# 5V_BOOST.net
KiCad netlist of a schematic drawn in Altium Designer
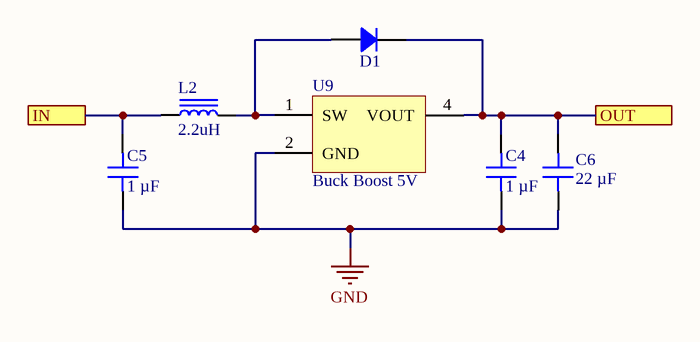
[diagram p0: 5V_BOOST.SchDoc]

(export (version "E")
  (design (tool "Eeschema 10.0.6"))
  (components
    (comp (ref "C4")
      (value "1 µF")
      (footprint "CAP 0402_1005")
      (description "CAP CER 0.1UF 16V X7R 0402")
      (fields (field (name "PART NUMBER") "C0402C104K4RACAUTO") (field (name "MANUFACTURER") "KEMET"))
      (libsource (lib "Celestial Altium Library - altium_library") (part "Capacitor"))
    )
    (comp (ref "C5")
      (value "1 µF")
      (footprint "CAP 0402_1005")
      (description "CAP CER 0.1UF 16V X7R 0402")
      (fields (field (name "PART NUMBER") "C0402C104K4RACAUTO") (field (name "MANUFACTURER") "KEMET"))
      (libsource (lib "Celestial Altium Library - altium_library") (part "Capacitor"))
    )
    (comp (ref "C6")
      (value "22 µF")
      (footprint "CAP 0805_2012")
      (description "CAP CER 22UF 10V X6S 0805")
      (fields
        (field (name "PART NUMBER") "GRM21BC81A226ME44L")
        (field (name "MANUFACTURER") "Murata Electronics")
      )
      (libsource (lib "Celestial Altium Library - altium_library") (part "Capacitor"))
    )
    (comp (ref "D1")
      (value "V1F6-M3/H")
      (footprint "SMF DO-219AB")
      (description "1A 60V SMF TRENCH SKY RECT")
      (fields (field (name "MANUFACTURER") "Vishay Semiconductor Diodes Division"))
      (libsource (lib "Celestial Altium Library - altium_library") (part "Diode"))
    )
    (comp (ref "L2")
      (value "2.2uH")
      (footprint "TAIYO YUDEN MAMK2520T1R0M")
      (description "FIXED IND 470NH 3.2A 46 MOHM SMD")
      (fields (field (name "PART NUMBER") "MAKK2520TR47M") (field (name "MANUFACTURER") "Taiyo Yuden"))
      (libsource (lib "Celestial Altium Library - altium_library") (part "Inductor"))
    )
    (comp (ref "U9")
      (value "Buck Boost 5V")
      (footprint "TI SOT-23-5 DBV")
      (description "ADJ step down Buck")
      (libsource (lib "IC") (part "TPS613222A"))
    )
  )
  (nets
    (net (code "1") (name "/IN") (class "Default")
      (node (ref "C5") (pin "2") (pinfunction "2_2") (pintype "passive"))
      (node (ref "L2") (pin "1") (pinfunction "1_1") (pintype "passive"))
    )
    (net (code "2") (name "/OUT") (class "Default")
      (node (ref "C4") (pin "2") (pinfunction "2_2") (pintype "passive"))
      (node (ref "C6") (pin "2") (pinfunction "2_2") (pintype "passive"))
      (node (ref "D1") (pin "2") (pinfunction "2_2") (pintype "passive"))
      (node (ref "U9") (pin "4") (pinfunction "VOUT_4") (pintype "passive"))
    )
    (net (code "3") (name "GND") (class "Default")
      (node (ref "C4") (pin "1") (pinfunction "1_1") (pintype "passive"))
      (node (ref "C5") (pin "1") (pinfunction "1_1") (pintype "passive"))
      (node (ref "C6") (pin "1") (pinfunction "1_1") (pintype "passive"))
      (node (ref "U9") (pin "2") (pinfunction "GND_2") (pintype "passive"))
    )
    (net (code "4") (name "Net-(U9-SW)") (class "Default")
      (node (ref "D1") (pin "1") (pinfunction "1_1") (pintype "passive"))
      (node (ref "L2") (pin "2") (pinfunction "2_2") (pintype "passive"))
      (node (ref "U9") (pin "1") (pinfunction "SW_1") (pintype "passive"))
    )
  )
)
